# 780-00029_rev2_Pg3_Backplane_Instrument_.net
KiCad netlist of a schematic drawn in Altium Designer
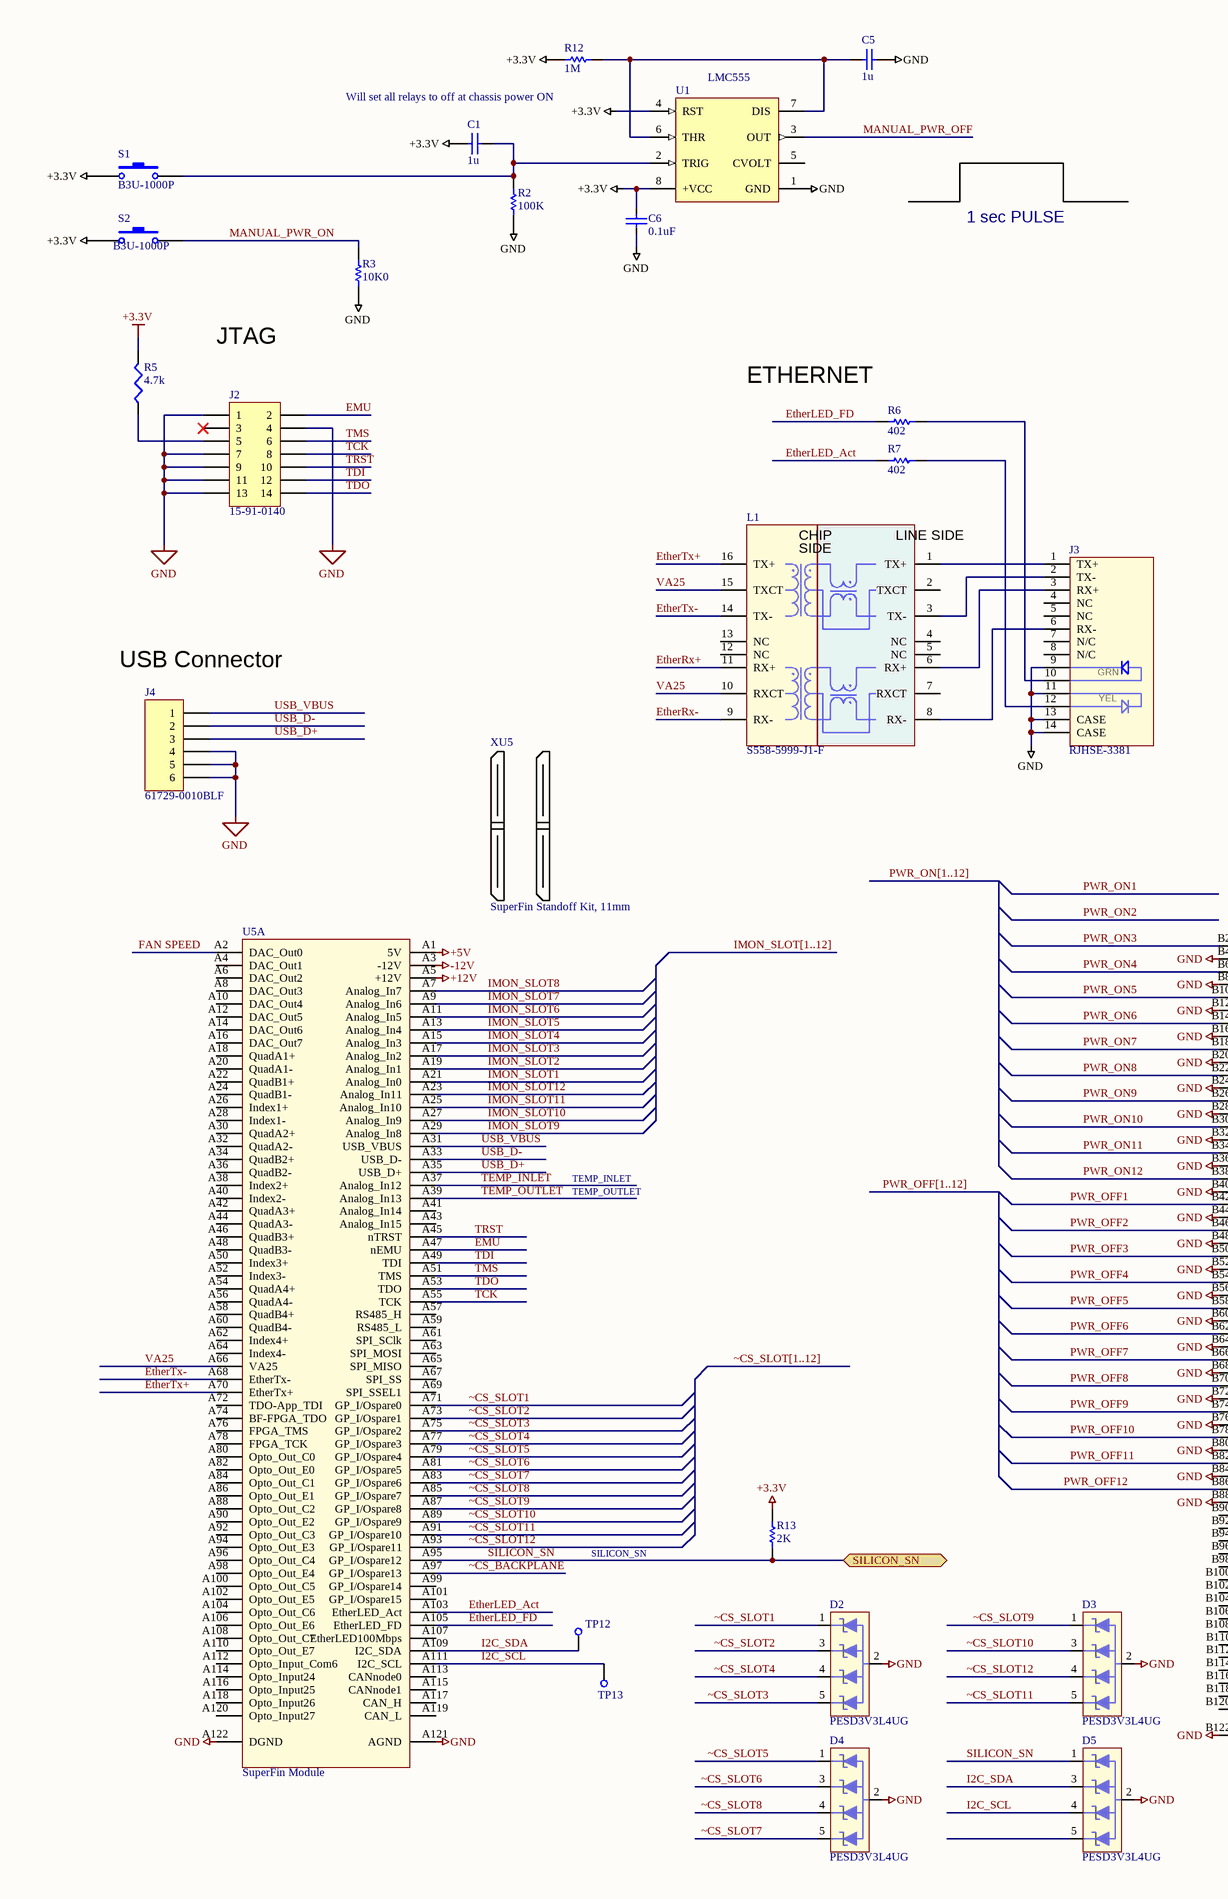
[diagram p0: 780-00029,rev2,Pg3,Backplane, Instrument Crate.SchDoc, left]
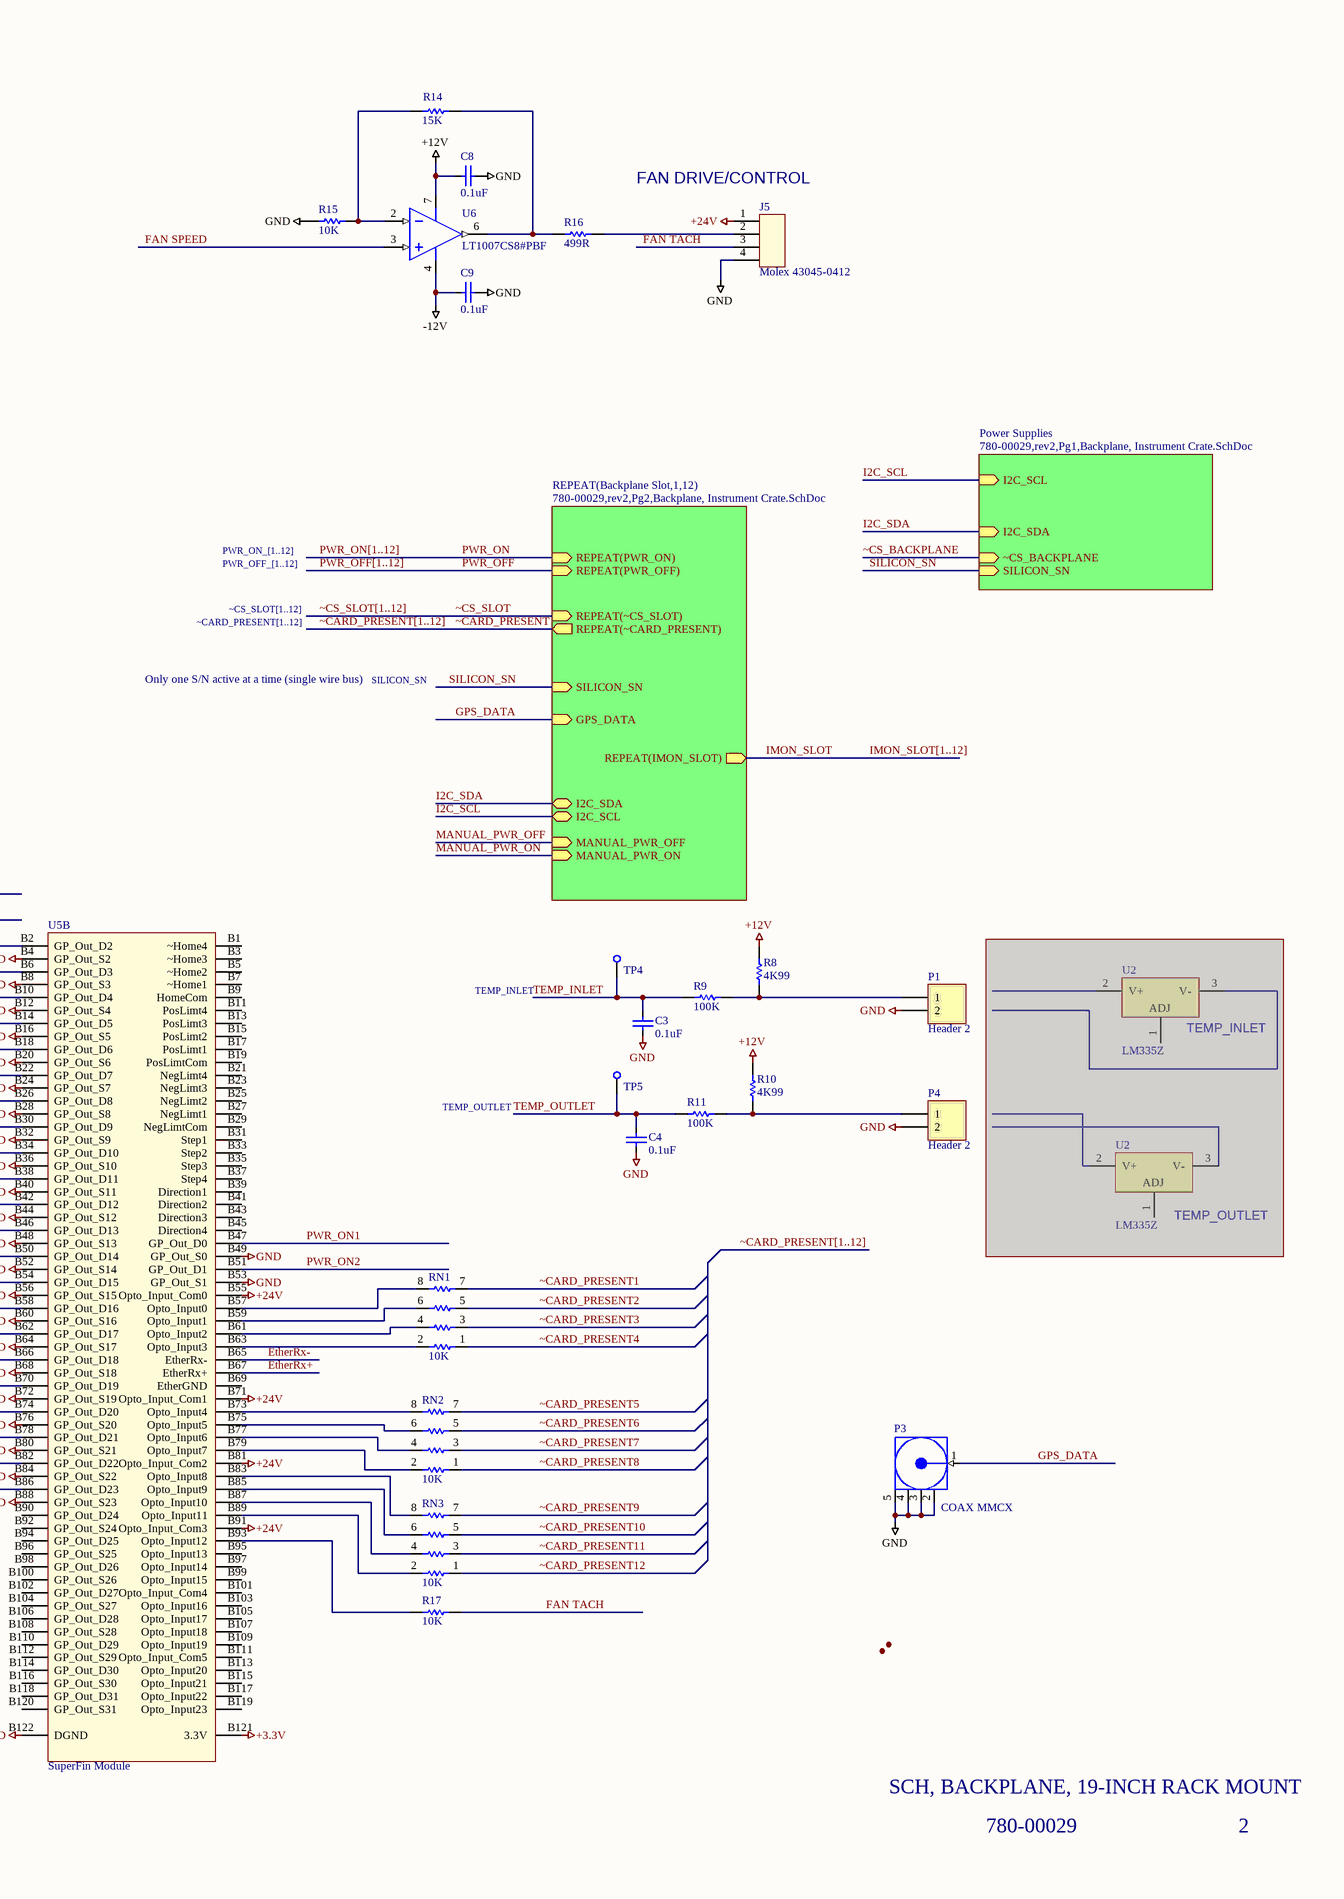
[diagram p1: 780-00029,rev2,Pg3,Backplane, Instrument Crate.SchDoc, right]

(export (version "E")
  (design (tool "Eeschema 10.0.6"))
  (components
    (comp (ref "C1")
      (value "1u")
      (footprint "2012[0805]")
      (description "Capacitor")
      (fields (field (name "MANUFACTURER") "Taiyo Yuden"))
      (libsource (lib "Miscellaneous Devices") (part "Cap"))
    )
    (comp (ref "C3")
      (value "0.1uF")
      (footprint "SMD_0805")
      (description "Capacitor")
      (fields (field (name "Comment") "Cap SMD"))
      (libsource (lib "Richs Schematic Components") (part "Cap SMD"))
    )
    (comp (ref "C4")
      (value "0.1uF")
      (footprint "SMD_0805")
      (description "Capacitor")
      (fields (field (name "Comment") "Cap SMD"))
      (libsource (lib "Richs Schematic Components") (part "Cap SMD"))
    )
    (comp (ref "C5")
      (value "1u")
      (footprint "SMD_0805")
      (description "Capacitor")
      (fields (field (name "MANUFACTURER") "Taiyo Yuden"))
      (libsource (lib "Miscellaneous Devices") (part "Cap"))
    )
    (comp (ref "C6")
      (value "0.1uF")
      (footprint "SMD_0805")
      (description "Capacitor")
      (fields (field (name "Comment") "Cap SMD"))
      (libsource (lib "Richs Schematic Components") (part "Cap SMD"))
    )
    (comp (ref "C8")
      (value "0.1uF")
      (footprint "SMD_0805")
      (description "Capacitor")
      (fields (field (name "Comment") "Cap SMD"))
      (libsource (lib "Richs Schematic Components") (part "Cap SMD"))
    )
    (comp (ref "C9")
      (value "0.1uF")
      (footprint "SMD_0805")
      (description "Capacitor")
      (fields (field (name "Comment") "Cap SMD"))
      (libsource (lib "Richs Schematic Components") (part "Cap SMD"))
    )
    (comp (ref "D2")
      (value "PESD3V3L4UG")
      (footprint "SOT-353")
      (description "Quad ESD Diode 3.3V")
      (fields (field (name "MANUFACTURER") "NXP"))
      (libsource (lib "Richs Schematic Components") (part "ESD Diode 3.3V Quad"))
    )
    (comp (ref "D3")
      (value "PESD3V3L4UG")
      (footprint "SOT-353")
      (description "Quad ESD Diode 3.3V")
      (fields (field (name "MANUFACTURER") "NXP"))
      (libsource (lib "Richs Schematic Components") (part "ESD Diode 3.3V Quad"))
    )
    (comp (ref "D4")
      (value "PESD3V3L4UG")
      (footprint "SOT-353")
      (description "Quad ESD Diode 3.3V")
      (fields (field (name "MANUFACTURER") "NXP"))
      (libsource (lib "Richs Schematic Components") (part "ESD Diode 3.3V Quad"))
    )
    (comp (ref "D5")
      (value "PESD3V3L4UG")
      (footprint "SOT-353")
      (description "Quad ESD Diode 3.3V")
      (fields (field (name "MANUFACTURER") "NXP"))
      (libsource (lib "Richs Schematic Components") (part "ESD Diode 3.3V Quad"))
    )
    (comp (ref "J2")
      (value "15-91-0140")
      (footprint "HDR2X7")
      (description "Header, 7-Pin, Dual row")
      (fields (field (name "MANUFACTURER") "Molex/Waldom"))
      (libsource (lib "Miscellaneous Connectors") (part "Header 7X2"))
    )
    (comp (ref "J3")
      (value "RJHSE-3381")
      (footprint "RJ45, VERT MOUNT, NO MAGNETICS")
      (description "Vertical PC mount, w/o magnetics")
      (libsource (lib "Richs Schematic Components") (part "CONN RJ-45 w/o magnetics"))
    )
    (comp (ref "J4")
      (value "61729-0010BLF")
      (footprint "USB Vertical PCB")
      (description "Header, 6-Pin")
      (fields (field (name "MANUFACTURER") "FCI"))
      (libsource (lib "Miscellaneous Connectors") (part "Header 6"))
    )
    (comp (ref "J5")
      (value "Molex 43045-0412")
      (footprint "CONN Molex Micro-fit, 4 POS")
      (description "Molex Micro Fit 3, Vert PC mount")
      (fields (field (name "MANUFACTURER") "Molex"))
      (libsource (lib "Richs Schematic Components") (part "CONN 4 pin 3mm"))
    )
    (comp (ref "L1")
      (value "S558-5999-J1-F")
      (footprint "10/100BT Magetics module")
      (description "10/100BT Magnetics Module")
      (libsource (lib "Richs Schematic Components") (part "Ethernet Magnetics module"))
    )
    (comp (ref "P1")
      (value "Header 2")
      (footprint "HDR1X2 for IDC")
      (description "Header, 2-Pin")
      (fields (field (name "MANUFACTURER") "TE Connectivity"))
      (libsource (lib "Richs Schematic Components") (part "Header 2"))
    )
    (comp (ref "P3")
      (value "COAX MMCX")
      (footprint "Miscellaneous Connectors:MMCX2.54-V5")
      (description "RF Coaxial PCB Connector, MMCX; Thru-Hole, Vertical Mount Plug,  50 Ohm Impedance")
      (fields (field (name "MANUFACTURER") "Emerson"))
      (libsource (lib "Richs Schematic Components") (part "COAX-M"))
    )
    (comp (ref "P4")
      (value "Header 2")
      (footprint "HDR1X2 for IDC")
      (description "Header, 2-Pin")
      (fields (field (name "MANUFACTURER") "TE Connectivity"))
      (libsource (lib "Richs Schematic Components") (part "Header 2"))
    )
    (comp (ref "R2")
      (value "100K")
      (footprint "SMD_0805")
      (description "Resistor 0805")
      (fields (field (name "MANUFACTURER") "Vishay/Dale") (field (name "Comment") "Res 0805"))
      (libsource (lib "Richs Schematic Components") (part "Res SMD"))
    )
    (comp (ref "R3")
      (value "10K0")
      (footprint "SMD_0805")
      (description "Resistor 0805")
      (fields (field (name "MANUFACTURER") "Vishay/Dale") (field (name "Comment") "Res 0805"))
      (libsource (lib "Richs Schematic Components") (part "Res SMD"))
    )
    (comp (ref "R5")
      (value "4.7k")
      (footprint "2012[0805]")
      (description "Resistor")
      (fields (field (name "MANUFACTURER") "Dale/Vishay"))
      (libsource (lib "Miscellaneous Devices") (part "Res3"))
    )
    (comp (ref "R6")
      (value "402")
      (footprint "SMD_0805")
      (description "Resistor 0805")
      (fields (field (name "MANUFACTURER") "Vishay/Dale") (field (name "Comment") "Res 0805"))
      (libsource (lib "Richs Schematic Components") (part "Res SMD"))
    )
    (comp (ref "R7")
      (value "402")
      (footprint "SMD_0805")
      (description "Resistor 0805")
      (fields (field (name "MANUFACTURER") "Vishay/Dale") (field (name "Comment") "Res 0805"))
      (libsource (lib "Richs Schematic Components") (part "Res SMD"))
    )
    (comp (ref "R8")
      (value "4K99")
      (footprint "SMD_0805")
      (description "Resistor 0805")
      (fields (field (name "MANUFACTURER") "Vishay/Dale") (field (name "Comment") "Res 0805"))
      (libsource (lib "Richs Schematic Components") (part "Res SMD"))
    )
    (comp (ref "R9")
      (value "100K")
      (footprint "SMD_0805")
      (description "Resistor 0805")
      (fields (field (name "MANUFACTURER") "Vishay/Dale") (field (name "Comment") "Res 0805"))
      (libsource (lib "Richs Schematic Components") (part "Res SMD"))
    )
    (comp (ref "R10")
      (value "4K99")
      (footprint "SMD_0805")
      (description "Resistor 0805")
      (fields (field (name "MANUFACTURER") "Vishay/Dale") (field (name "Comment") "Res 0805"))
      (libsource (lib "Richs Schematic Components") (part "Res SMD"))
    )
    (comp (ref "R11")
      (value "100K")
      (footprint "SMD_0805")
      (description "Resistor 0805")
      (fields (field (name "MANUFACTURER") "Vishay/Dale") (field (name "Comment") "Res 0805"))
      (libsource (lib "Richs Schematic Components") (part "Res SMD"))
    )
    (comp (ref "R12")
      (value "1M")
      (footprint "SMD_0805")
      (description "Resistor 0805")
      (fields (field (name "MANUFACTURER") "Vishay/Dale") (field (name "Comment") "Res 0805"))
      (libsource (lib "Richs Schematic Components") (part "Res SMD"))
    )
    (comp (ref "R13")
      (value "2K")
      (footprint "SMD_0805")
      (description "Resistor 0805")
      (fields (field (name "MANUFACTURER") "Vishay/Dale") (field (name "Comment") "Res 0805"))
      (libsource (lib "Richs Schematic Components") (part "Res SMD"))
    )
    (comp (ref "R14")
      (value "15K")
      (footprint "SMD_0805")
      (description "Resistor 0805")
      (fields (field (name "MANUFACTURER") "Vishay/Dale") (field (name "Comment") "Res 0805"))
      (libsource (lib "Richs Schematic Components") (part "Res SMD"))
    )
    (comp (ref "R15")
      (value "10K")
      (footprint "SMD_0805")
      (description "Resistor 0805")
      (fields (field (name "MANUFACTURER") "Vishay/Dale") (field (name "Comment") "Res 0805"))
      (libsource (lib "Richs Schematic Components") (part "Res SMD"))
    )
    (comp (ref "R16")
      (value "499R")
      (footprint "SMD_0805")
      (description "Resistor 0805")
      (fields (field (name "MANUFACTURER") "Vishay/Dale") (field (name "Comment") "Res 0805"))
      (libsource (lib "Richs Schematic Components") (part "Res SMD"))
    )
    (comp (ref "R17")
      (value "10K")
      (footprint "SMD_0805")
      (description "Resistor 0805")
      (fields (field (name "MANUFACTURER") "Vishay/Dale") (field (name "Comment") "Res 0805"))
      (libsource (lib "Richs Schematic Components") (part "Res SMD"))
    )
    (comp (ref "RN1")
      (value "10K")
      (footprint "RES ARRAY 0603 x 4")
      (description "Resistor Array 4 Isolated")
      (fields (field (name "MANUFACTURER") "PANASONIC - ECG") (field (name "Comment") "RES ARRAY  x4 10K"))
      (libsource (lib "Richs Schematic Components") (part "RES ARRAY  x4 10K"))
    )
    (comp (ref "RN2")
      (value "10K")
      (footprint "RES ARRAY 0603 x 4")
      (description "Resistor Array 4 Isolated")
      (fields (field (name "MANUFACTURER") "PANASONIC - ECG") (field (name "Comment") "RES ARRAY  x4 10K"))
      (libsource (lib "Richs Schematic Components") (part "RES ARRAY  x4 10K"))
    )
    (comp (ref "RN3")
      (value "10K")
      (footprint "RES ARRAY 0603 x 4")
      (description "Resistor Array 4 Isolated")
      (fields (field (name "MANUFACTURER") "PANASONIC - ECG") (field (name "Comment") "RES ARRAY  x4 10K"))
      (libsource (lib "Richs Schematic Components") (part "RES ARRAY  x4 10K"))
    )
    (comp (ref "S1")
      (value "B3U-1000P")
      (footprint "B3U-1000P")
      (description "Switch")
      (fields (field (name "MANUFACTURER") "Omron Electronics"))
      (libsource (lib "Miscellaneous Devices") (part "SW-PB"))
    )
    (comp (ref "S2")
      (value "B3U-1000P")
      (footprint "B3U-1000P")
      (description "Switch")
      (fields (field (name "MANUFACTURER") "Omron Electronics"))
      (libsource (lib "Miscellaneous Devices") (part "SW-PB"))
    )
    (comp (ref "TP4")
      (value "Test Point SMD")
      (footprint "SMD_TEST POINT")
      (description "SMD loop test point")
      (libsource (lib "Richs Schematic Components") (part "Test Point SMD"))
    )
    (comp (ref "TP5")
      (value "Test Point SMD")
      (footprint "SMD_TEST POINT")
      (description "SMD loop test point")
      (libsource (lib "Richs Schematic Components") (part "Test Point SMD"))
    )
    (comp (ref "TP12")
      (value "Test Point SMD")
      (footprint "SMD_TEST POINT")
      (description "SMD loop test point")
      (libsource (lib "Richs Schematic Components") (part "Test Point SMD"))
    )
    (comp (ref "TP13")
      (value "Test Point SMD")
      (footprint "SMD_TEST POINT")
      (description "SMD loop test point")
      (libsource (lib "Richs Schematic Components") (part "Test Point SMD"))
    )
    (comp (ref "U1")
      (value "LMC555")
      (footprint "M08A_M")
      (description "Timer")
      (fields (field (name "MANUFACTURER") "National Semiconductor") (field (name "Comment") "LM555CMX"))
      (libsource (lib "NSC Analog") (part "LM555CMX"))
    )
    (comp (ref "U2")
      (value "LM335Z")
      (footprint "Z03A")
      (description "Precision Temperature Sensor")
      (fields (field (name "MANUFACTURER") "National Semiconductor"))
      (libsource (lib "NSC Temperature Sensor") (part "LM335Z"))
    )
    (comp (ref "U5")
      (value "SuperFin Module")
      (footprint "SuperFin Footprint")
      (libsource (lib "Richs Schematic Components") (part "SuperFin Module"))
    )
    (comp (ref "U6")
      (value "LT1007CS8#PBF")
      (footprint "S8_M")
      (description "Low Noise BJT input opamp")
      (fields (field (name "MANUFACTURER") "Linear Tech"))
      (libsource (lib "Richs Schematic Components") (part "LT1007CS8#PBF"))
    )
    (comp (ref "XU5")
      (value "SuperFin Standoff Kit, 11mm")
      (libsource (lib "Richs Schematic Components") (part "SuperFin Standoff Kit, 11mm"))
    )
  )
  (nets
    (net (code "1") (name "+3.3V") (class "Default")
      (node (ref "C1") (pin "1") (pinfunction "1_1") (pintype "passive"))
      (node (ref "C6") (pin "2") (pinfunction "2_2") (pintype "passive"))
      (node (ref "R12") (pin "1") (pinfunction "1_1") (pintype "passive"))
      (node (ref "R13") (pin "2") (pinfunction "2_2") (pintype "passive"))
      (node (ref "R5") (pin "2") (pinfunction "2_2") (pintype "passive"))
      (node (ref "S1") (pin "1") (pinfunction "1_1") (pintype "passive"))
      (node (ref "S2") (pin "1") (pinfunction "1_1") (pintype "passive"))
      (node (ref "U1") (pin "4") (pinfunction "RST_4") (pintype "input"))
      (node (ref "U1") (pin "8") (pinfunction "+VCC_8") (pintype "power_in"))
      (node (ref "U5") (pin "B121") (pinfunction "3.3V_B121") (pintype "passive"))
    )
    (net (code "2") (name "+5V") (class "Default")
      (node (ref "U5") (pin "A1") (pinfunction "5V_A1") (pintype "passive"))
    )
    (net (code "3") (name "+12V") (class "Default")
      (node (ref "C8") (pin "1") (pinfunction "1_1") (pintype "passive"))
      (node (ref "R10") (pin "2") (pinfunction "2_2") (pintype "passive"))
      (node (ref "R8") (pin "2") (pinfunction "2_2") (pintype "passive"))
      (node (ref "U5") (pin "A5") (pinfunction "+12V_A5") (pintype "passive"))
      (node (ref "U6") (pin "7") (pinfunction "V+_7") (pintype "power_in"))
    )
    (net (code "4") (name "+24V") (class "Default")
      (node (ref "J5") (pin "1") (pintype "passive"))
      (node (ref "U5") (pin "B55") (pinfunction "Opto_Input_Com0_B55") (pintype "passive"))
      (node (ref "U5") (pin "B71") (pinfunction "Opto_Input_Com1_B71") (pintype "passive"))
      (node (ref "U5") (pin "B81") (pinfunction "Opto_Input_Com2_B81") (pintype "passive"))
      (node (ref "U5") (pin "B91") (pinfunction "Opto_Input_Com3_B91") (pintype "passive"))
    )
    (net (code "5") (name "-12V") (class "Default")
      (node (ref "C9") (pin "1") (pinfunction "1_1") (pintype "passive"))
      (node (ref "U5") (pin "A3") (pinfunction "-12V_A3") (pintype "passive"))
      (node (ref "U6") (pin "4") (pinfunction "V-_4") (pintype "power_in"))
    )
    (net (code "6") (name "/EMU") (class "Default")
      (node (ref "J2") (pin "2") (pinfunction "2_2") (pintype "passive"))
      (node (ref "U5") (pin "A47") (pinfunction "nEMU_A47") (pintype "passive"))
    )
    (net (code "7") (name "/EtherLED_Act") (class "Default")
      (node (ref "R7") (pin "1") (pinfunction "1_1") (pintype "passive"))
      (node (ref "U5") (pin "A103") (pinfunction "EtherLED_Act_A103") (pintype "passive"))
    )
    (net (code "8") (name "/EtherLED_FD") (class "Default")
      (node (ref "R6") (pin "1") (pinfunction "1_1") (pintype "passive"))
      (node (ref "U5") (pin "A105") (pinfunction "EtherLED_FD_A105") (pintype "passive"))
    )
    (net (code "9") (name "/EtherRx+") (class "Default")
      (node (ref "L1") (pin "11") (pinfunction "RX+_11") (pintype "passive"))
      (node (ref "U5") (pin "B67") (pinfunction "EtherRx+_B67") (pintype "passive"))
    )
    (net (code "10") (name "/EtherRx-") (class "Default")
      (node (ref "L1") (pin "9") (pinfunction "RX-_9") (pintype "passive"))
      (node (ref "U5") (pin "B65") (pinfunction "EtherRx-_B65") (pintype "passive"))
    )
    (net (code "11") (name "/EtherTx+") (class "Default")
      (node (ref "L1") (pin "16") (pinfunction "TX+_16") (pintype "passive"))
      (node (ref "U5") (pin "A70") (pinfunction "EtherTx+_A70") (pintype "passive"))
    )
    (net (code "12") (name "/EtherTx-") (class "Default")
      (node (ref "L1") (pin "14") (pinfunction "TX-_14") (pintype "passive"))
      (node (ref "U5") (pin "A68") (pinfunction "EtherTx-_A68") (pintype "passive"))
    )
    (net (code "13") (name "/FAN SPEED") (class "Default")
      (node (ref "U5") (pin "A2") (pinfunction "DAC_Out0_A2") (pintype "passive"))
      (node (ref "U6") (pin "3") (pinfunction "IN+_3") (pintype "input"))
    )
    (net (code "14") (name "/FAN TACH") (class "Default")
      (node (ref "J5") (pin "3") (pintype "passive"))
      (node (ref "R17") (pin "2") (pinfunction "2_2") (pintype "passive"))
    )
    (net (code "15") (name "/GPS_DATA") (class "Default")
      (node (ref "P3") (pin "1") (pinfunction "Signal_1") (pintype "input"))
    )
    (net (code "16") (name "/I2C_SCL") (class "Default")
      (node (ref "D5") (pin "4") (pintype "passive"))
      (node (ref "TP13") (pin "1") (pinfunction "TP_1") (pintype "passive"))
      (node (ref "U5") (pin "A111") (pinfunction "I2C_SCL_A111") (pintype "passive"))
    )
    (net (code "17") (name "/I2C_SDA") (class "Default")
      (node (ref "D5") (pin "3") (pintype "passive"))
      (node (ref "TP12") (pin "1") (pinfunction "TP_1") (pintype "passive"))
      (node (ref "U5") (pin "A109") (pinfunction "I2C_SDA_A109") (pintype "passive"))
    )
    (net (code "19") (name "/IMON_SLOT1") (class "Default")
      (node (ref "U5") (pin "A21") (pinfunction "Analog_In0_A21") (pintype "passive"))
    )
    (net (code "20") (name "/IMON_SLOT2") (class "Default")
      (node (ref "U5") (pin "A19") (pinfunction "Analog_In1_A19") (pintype "passive"))
    )
    (net (code "21") (name "/IMON_SLOT3") (class "Default")
      (node (ref "U5") (pin "A17") (pinfunction "Analog_In2_A17") (pintype "passive"))
    )
    (net (code "22") (name "/IMON_SLOT4") (class "Default")
      (node (ref "U5") (pin "A15") (pinfunction "Analog_In3_A15") (pintype "passive"))
    )
    (net (code "23") (name "/IMON_SLOT5") (class "Default")
      (node (ref "U5") (pin "A13") (pinfunction "Analog_In4_A13") (pintype "passive"))
    )
    (net (code "24") (name "/IMON_SLOT6") (class "Default")
      (node (ref "U5") (pin "A11") (pinfunction "Analog_In5_A11") (pintype "passive"))
    )
    (net (code "25") (name "/IMON_SLOT7") (class "Default")
      (node (ref "U5") (pin "A9") (pinfunction "Analog_In6_A9") (pintype "passive"))
    )
    (net (code "26") (name "/IMON_SLOT8") (class "Default")
      (node (ref "U5") (pin "A7") (pinfunction "Analog_In7_A7") (pintype "passive"))
    )
    (net (code "27") (name "/IMON_SLOT9") (class "Default")
      (node (ref "U5") (pin "A29") (pinfunction "Analog_In8_A29") (pintype "passive"))
    )
    (net (code "28") (name "/IMON_SLOT10") (class "Default")
      (node (ref "U5") (pin "A27") (pinfunction "Analog_In9_A27") (pintype "passive"))
    )
    (net (code "29") (name "/IMON_SLOT11") (class "Default")
      (node (ref "U5") (pin "A25") (pinfunction "Analog_In10_A25") (pintype "passive"))
    )
    (net (code "30") (name "/IMON_SLOT12") (class "Default")
      (node (ref "U5") (pin "A23") (pinfunction "Analog_In11_A23") (pintype "passive"))
    )
    (net (code "32") (name "/MANUAL_PWR_OFF") (class "Default")
      (node (ref "U1") (pin "3") (pinfunction "OUT_3") (pintype "output"))
    )
    (net (code "33") (name "/MANUAL_PWR_ON") (class "Default")
      (node (ref "R3") (pin "2") (pinfunction "2_2") (pintype "passive"))
      (node (ref "S2") (pin "2") (pinfunction "2_2") (pintype "passive"))
    )
    (net (code "35") (name "/PWR_OFF1") (class "Default")
      (node (ref "U5") (pin "B42") (pinfunction "GP_Out_D12_B42") (pintype "passive"))
    )
    (net (code "36") (name "/PWR_OFF2") (class "Default")
      (node (ref "U5") (pin "B46") (pinfunction "GP_Out_D13_B46") (pintype "passive"))
    )
    (net (code "37") (name "/PWR_OFF3") (class "Default")
      (node (ref "U5") (pin "B50") (pinfunction "GP_Out_D14_B50") (pintype "passive"))
    )
    (net (code "38") (name "/PWR_OFF4") (class "Default")
      (node (ref "U5") (pin "B54") (pinfunction "GP_Out_D15_B54") (pintype "passive"))
    )
    (net (code "39") (name "/PWR_OFF5") (class "Default")
      (node (ref "U5") (pin "B58") (pinfunction "GP_Out_D16_B58") (pintype "passive"))
    )
    (net (code "40") (name "/PWR_OFF6") (class "Default")
      (node (ref "U5") (pin "B62") (pinfunction "GP_Out_D17_B62") (pintype "passive"))
    )
    (net (code "41") (name "/PWR_OFF7") (class "Default")
      (node (ref "U5") (pin "B66") (pinfunction "GP_Out_D18_B66") (pintype "passive"))
    )
    (net (code "42") (name "/PWR_OFF8") (class "Default")
      (node (ref "U5") (pin "B70") (pinfunction "GP_Out_D19_B70") (pintype "passive"))
    )
    (net (code "43") (name "/PWR_OFF9") (class "Default")
      (node (ref "U5") (pin "B74") (pinfunction "GP_Out_D20_B74") (pintype "passive"))
    )
    (net (code "44") (name "/PWR_OFF10") (class "Default")
      (node (ref "U5") (pin "B78") (pinfunction "GP_Out_D21_B78") (pintype "passive"))
    )
    (net (code "45") (name "/PWR_OFF11") (class "Default")
      (node (ref "U5") (pin "B82") (pinfunction "GP_Out_D22_B82") (pintype "passive"))
    )
    (net (code "46") (name "/PWR_OFF12") (class "Default")
      (node (ref "U5") (pin "B86") (pinfunction "GP_Out_D23_B86") (pintype "passive"))
    )
    (net (code "49") (name "/PWR_ON1") (class "Default")
      (node (ref "U5") (pin "B47") (pinfunction "GP_Out_D0_B47") (pintype "passive"))
    )
    (net (code "50") (name "/PWR_ON2") (class "Default")
      (node (ref "U5") (pin "B51") (pinfunction "GP_Out_D1_B51") (pintype "passive"))
    )
    (net (code "51") (name "/PWR_ON3") (class "Default")
      (node (ref "U5") (pin "B2") (pinfunction "GP_Out_D2_B2") (pintype "passive"))
    )
    (net (code "52") (name "/PWR_ON4") (class "Default")
      (node (ref "U5") (pin "B6") (pinfunction "GP_Out_D3_B6") (pintype "passive"))
    )
    (net (code "53") (name "/PWR_ON5") (class "Default")
      (node (ref "U5") (pin "B10") (pinfunction "GP_Out_D4_B10") (pintype "passive"))
    )
    (net (code "54") (name "/PWR_ON6") (class "Default")
      (node (ref "U5") (pin "B14") (pinfunction "GP_Out_D5_B14") (pintype "passive"))
    )
    (net (code "55") (name "/PWR_ON7") (class "Default")
      (node (ref "U5") (pin "B18") (pinfunction "GP_Out_D6_B18") (pintype "passive"))
    )
    (net (code "56") (name "/PWR_ON8") (class "Default")
      (node (ref "U5") (pin "B22") (pinfunction "GP_Out_D7_B22") (pintype "passive"))
    )
    (net (code "57") (name "/PWR_ON9") (class "Default")
      (node (ref "U5") (pin "B26") (pinfunction "GP_Out_D8_B26") (pintype "passive"))
    )
    (net (code "58") (name "/PWR_ON10") (class "Default")
      (node (ref "U5") (pin "B30") (pinfunction "GP_Out_D9_B30") (pintype "passive"))
    )
    (net (code "59") (name "/PWR_ON11") (class "Default")
      (node (ref "U5") (pin "B34") (pinfunction "GP_Out_D10_B34") (pintype "passive"))
    )
    (net (code "60") (name "/PWR_ON12") (class "Default")
      (node (ref "U5") (pin "B38") (pinfunction "GP_Out_D11_B38") (pintype "passive"))
    )
    (net (code "62") (name "/SILICON_SN") (class "Default")
      (node (ref "D5") (pin "1") (pintype "passive"))
      (node (ref "R13") (pin "1") (pinfunction "1_1") (pintype "passive"))
      (node (ref "U5") (pin "A95") (pinfunction "GP_I/Ospare12_A95") (pintype "passive"))
    )
    (net (code "63") (name "/TCK") (class "Default")
      (node (ref "J2") (pin "8") (pinfunction "8_8") (pintype "passive"))
      (node (ref "U5") (pin "A55") (pinfunction "TCK_A55") (pintype "passive"))
    )
    (net (code "64") (name "/TDI") (class "Default")
      (node (ref "J2") (pin "12") (pinfunction "12_12") (pintype "passive"))
      (node (ref "U5") (pin "A49") (pinfunction "TDI_A49") (pintype "passive"))
    )
    (net (code "65") (name "/TDO") (class "Default")
      (node (ref "J2") (pin "14") (pinfunction "14_14") (pintype "passive"))
      (node (ref "U5") (pin "A53") (pinfunction "TDO_A53") (pintype "passive"))
    )
    (net (code "66") (name "/TEMP_INLET") (class "Default")
      (node (ref "C3") (pin "2") (pinfunction "2_2") (pintype "passive"))
      (node (ref "R9") (pin "1") (pinfunction "1_1") (pintype "passive"))
      (node (ref "TP4") (pin "1") (pinfunction "TP_1") (pintype "passive"))
      (node (ref "U5") (pin "A37") (pinfunction "Analog_In12_A37") (pintype "passive"))
    )
    (net (code "67") (name "/TEMP_OUTLET") (class "Default")
      (node (ref "C4") (pin "2") (pinfunction "2_2") (pintype "passive"))
      (node (ref "R11") (pin "1") (pinfunction "1_1") (pintype "passive"))
      (node (ref "TP5") (pin "1") (pinfunction "TP_1") (pintype "passive"))
      (node (ref "U5") (pin "A39") (pinfunction "Analog_In13_A39") (pintype "passive"))
    )
    (net (code "68") (name "/TMS") (class "Default")
      (node (ref "J2") (pin "6") (pinfunction "6_6") (pintype "passive"))
      (node (ref "U5") (pin "A51") (pinfunction "TMS_A51") (pintype "passive"))
    )
    (net (code "69") (name "/TRST") (class "Default")
      (node (ref "J2") (pin "10") (pinfunction "10_10") (pintype "passive"))
      (node (ref "U5") (pin "A45") (pinfunction "nTRST_A45") (pintype "passive"))
    )
    (net (code "70") (name "/USB_D+") (class "Default")
      (node (ref "J4") (pin "3") (pinfunction "3_3") (pintype "passive"))
      (node (ref "U5") (pin "A35") (pinfunction "USB_D+_A35") (pintype "passive"))
    )
    (net (code "71") (name "/USB_D-") (class "Default")
      (node (ref "J4") (pin "2") (pinfunction "2_2") (pintype "passive"))
      (node (ref "U5") (pin "A33") (pinfunction "USB_D-_A33") (pintype "passive"))
    )
    (net (code "72") (name "/USB_VBUS") (class "Default")
      (node (ref "J4") (pin "1") (pinfunction "1_1") (pintype "passive"))
      (node (ref "U5") (pin "A31") (pinfunction "USB_VBUS_A31") (pintype "passive"))
    )
    (net (code "73") (name "/VA25") (class "Default")
      (node (ref "L1") (pin "10") (pinfunction "RXCT_10") (pintype "passive"))
      (node (ref "L1") (pin "15") (pinfunction "TXCT_15") (pintype "passive"))
      (node (ref "U5") (pin "A66") (pinfunction "VA25_A66") (pintype "passive"))
    )
    (net (code "75") (name "/~CARD_PRESENT1") (class "Default")
      (node (ref "RN1") (pin "7") (pinfunction "1_7") (pintype "passive"))
    )
    (net (code "76") (name "/~CARD_PRESENT2") (class "Default")
      (node (ref "RN1") (pin "5") (pinfunction "5_5") (pintype "passive"))
    )
    (net (code "77") (name "/~CARD_PRESENT3") (class "Default")
      (node (ref "RN1") (pin "3") (pinfunction "3_3") (pintype "passive"))
    )
    (net (code "78") (name "/~CARD_PRESENT4") (class "Default")
      (node (ref "RN1") (pin "1") (pinfunction "1_1") (pintype "passive"))
    )
    (net (code "79") (name "/~CARD_PRESENT5") (class "Default")
      (node (ref "RN2") (pin "7") (pinfunction "1_7") (pintype "passive"))
    )
    (net (code "80") (name "/~CARD_PRESENT6") (class "Default")
      (node (ref "RN2") (pin "5") (pinfunction "5_5") (pintype "passive"))
    )
    (net (code "81") (name "/~CARD_PRESENT7") (class "Default")
      (node (ref "RN2") (pin "3") (pinfunction "3_3") (pintype "passive"))
    )
    (net (code "82") (name "/~CARD_PRESENT8") (class "Default")
      (node (ref "RN2") (pin "1") (pinfunction "1_1") (pintype "passive"))
    )
    (net (code "83") (name "/~CARD_PRESENT9") (class "Default")
      (node (ref "RN3") (pin "7") (pinfunction "1_7") (pintype "passive"))
    )
    (net (code "84") (name "/~CARD_PRESENT10") (class "Default")
      (node (ref "RN3") (pin "5") (pinfunction "5_5") (pintype "passive"))
    )
    (net (code "85") (name "/~CARD_PRESENT11") (class "Default")
      (node (ref "RN3") (pin "3") (pinfunction "3_3") (pintype "passive"))
    )
    (net (code "86") (name "/~CARD_PRESENT12") (class "Default")
      (node (ref "RN3") (pin "1") (pinfunction "1_1") (pintype "passive"))
    )
    (net (code "88") (name "/~CS_BACKPLANE") (class "Default")
      (node (ref "U5") (pin "A97") (pinfunction "GP_I/Ospare13_A97") (pintype "passive"))
    )
    (net (code "90") (name "/~CS_SLOT1") (class "Default")
      (node (ref "D2") (pin "1") (pintype "passive"))
      (node (ref "U5") (pin "A71") (pinfunction "GP_I/Ospare0_A71") (pintype "passive"))
    )
    (net (code "91") (name "/~CS_SLOT2") (class "Default")
      (node (ref "D2") (pin "3") (pintype "passive"))
      (node (ref "U5") (pin "A73") (pinfunction "GP_I/Ospare1_A73") (pintype "passive"))
    )
    (net (code "92") (name "/~CS_SLOT3") (class "Default")
      (node (ref "D2") (pin "5") (pintype "passive"))
      (node (ref "U5") (pin "A75") (pinfunction "GP_I/Ospare2_A75") (pintype "passive"))
    )
    (net (code "93") (name "/~CS_SLOT4") (class "Default")
      (node (ref "D2") (pin "4") (pintype "passive"))
      (node (ref "U5") (pin "A77") (pinfunction "GP_I/Ospare3_A77") (pintype "passive"))
    )
    (net (code "94") (name "/~CS_SLOT5") (class "Default")
      (node (ref "D4") (pin "1") (pintype "passive"))
      (node (ref "U5") (pin "A79") (pinfunction "GP_I/Ospare4_A79") (pintype "passive"))
    )
    (net (code "95") (name "/~CS_SLOT6") (class "Default")
      (node (ref "D4") (pin "3") (pintype "passive"))
      (node (ref "U5") (pin "A81") (pinfunction "GP_I/Ospare5_A81") (pintype "passive"))
    )
    (net (code "96") (name "/~CS_SLOT7") (class "Default")
      (node (ref "D4") (pin "5") (pintype "passive"))
      (node (ref "U5") (pin "A83") (pinfunction "GP_I/Ospare6_A83") (pintype "passive"))
    )
    (net (code "97") (name "/~CS_SLOT8") (class "Default")
      (node (ref "D4") (pin "4") (pintype "passive"))
      (node (ref "U5") (pin "A85") (pinfunction "GP_I/Ospare7_A85") (pintype "passive"))
    )
    (net (code "98") (name "/~CS_SLOT9") (class "Default")
      (node (ref "D3") (pin "1") (pintype "passive"))
      (node (ref "U5") (pin "A87") (pinfunction "GP_I/Ospare8_A87") (pintype "passive"))
    )
    (net (code "99") (name "/~CS_SLOT10") (class "Default")
      (node (ref "D3") (pin "3") (pintype "passive"))
      (node (ref "U5") (pin "A89") (pinfunction "GP_I/Ospare9_A89") (pintype "passive"))
    )
    (net (code "100") (name "/~CS_SLOT11") (class "Default")
      (node (ref "D3") (pin "5") (pintype "passive"))
      (node (ref "U5") (pin "A91") (pinfunction "GP_I/Ospare10_A91") (pintype "passive"))
    )
    (net (code "101") (name "/~CS_SLOT12") (class "Default")
      (node (ref "D3") (pin "4") (pintype "passive"))
      (node (ref "U5") (pin "A93") (pinfunction "GP_I/Ospare11_A93") (pintype "passive"))
    )
    (net (code "103") (name "GND") (class "Default")
      (node (ref "C3") (pin "1") (pinfunction "1_1") (pintype "passive"))
      (node (ref "C4") (pin "1") (pinfunction "1_1") (pintype "passive"))
      (node (ref "C5") (pin "2") (pinfunction "2_2") (pintype "passive"))
      (node (ref "C6") (pin "1") (pinfunction "1_1") (pintype "passive"))
      (node (ref "C8") (pin "2") (pinfunction "2_2") (pintype "passive"))
      (node (ref "C9") (pin "2") (pinfunction "2_2") (pintype "passive"))
      (node (ref "D2") (pin "2") (pintype "passive"))
      (node (ref "D3") (pin "2") (pintype "passive"))
      (node (ref "D4") (pin "2") (pintype "passive"))
      (node (ref "D5") (pin "2") (pintype "passive"))
      (node (ref "J2") (pin "1") (pinfunction "1_1") (pintype "passive"))
      (node (ref "J2") (pin "11") (pinfunction "11_11") (pintype "passive"))
      (node (ref "J2") (pin "13") (pinfunction "13_13") (pintype "passive"))
      (node (ref "J2") (pin "4") (pinfunction "4_4") (pintype "passive"))
      (node (ref "J2") (pin "7") (pinfunction "7_7") (pintype "passive"))
      (node (ref "J2") (pin "9") (pinfunction "9_9") (pintype "passive"))
      (node (ref "J3") (pin "11") (pinfunction "YEL-Cathode_11") (pintype "passive"))
      (node (ref "J3") (pin "13") (pinfunction "CASE_13") (pintype "passive"))
      (node (ref "J3") (pin "14") (pinfunction "CASE_14") (pintype "passive"))
      (node (ref "J3") (pin "9") (pinfunction "GRN-Anode_9") (pintype "passive"))
      (node (ref "J4") (pin "4") (pinfunction "4_4") (pintype "passive"))
      (node (ref "J4") (pin "5") (pinfunction "5_5") (pintype "passive"))
      (node (ref "J4") (pin "6") (pinfunction "6_6") (pintype "passive"))
      (node (ref "J5") (pin "4") (pintype "passive"))
      (node (ref "P1") (pin "2") (pinfunction "2_2") (pintype "passive"))
      (node (ref "P3") (pin "2") (pinfunction "GND_2") (pintype "power_in"))
      (node (ref "P3") (pin "3") (pinfunction "GND_3") (pintype "power_in"))
      (node (ref "P3") (pin "4") (pinfunction "GND_4") (pintype "power_in"))
      (node (ref "P3") (pin "5") (pinfunction "GND_5") (pintype "power_in"))
      (node (ref "P4") (pin "2") (pinfunction "2_2") (pintype "passive"))
      (node (ref "R15") (pin "1") (pinfunction "1_1") (pintype "passive"))
      (node (ref "R2") (pin "1") (pinfunction "1_1") (pintype "passive"))
      (node (ref "R3") (pin "1") (pinfunction "1_1") (pintype "passive"))
      (node (ref "U1") (pin "1") (pinfunction "GND_1") (pintype "power_in"))
      (node (ref "U5") (pin "A121") (pinfunction "AGND_A121") (pintype "passive"))
      (node (ref "U5") (pin "A122") (pinfunction "DGND_A122") (pintype "passive"))
      (node (ref "U5") (pin "B12") (pinfunction "GP_Out_S4_B12") (pintype "passive"))
      (node (ref "U5") (pin "B122") (pinfunction "DGND_B122") (pintype "passive"))
      (node (ref "U5") (pin "B16") (pinfunction "GP_Out_S5_B16") (pintype "passive"))
      (node (ref "U5") (pin "B20") (pinfunction "GP_Out_S6_B20") (pintype "passive"))
      (node (ref "U5") (pin "B24") (pinfunction "GP_Out_S7_B24") (pintype "passive"))
      (node (ref "U5") (pin "B28") (pinfunction "GP_Out_S8_B28") (pintype "passive"))
      (node (ref "U5") (pin "B32") (pinfunction "GP_Out_S9_B32") (pintype "passive"))
      (node (ref "U5") (pin "B36") (pinfunction "GP_Out_S10_B36") (pintype "passive"))
      (node (ref "U5") (pin "B4") (pinfunction "GP_Out_S2_B4") (pintype "passive"))
      (node (ref "U5") (pin "B40") (pinfunction "GP_Out_S11_B40") (pintype "passive"))
      (node (ref "U5") (pin "B44") (pinfunction "GP_Out_S12_B44") (pintype "passive"))
      (node (ref "U5") (pin "B48") (pinfunction "GP_Out_S13_B48") (pintype "passive"))
      (node (ref "U5") (pin "B49") (pinfunction "GP_Out_S0_B49") (pintype "passive"))
      (node (ref "U5") (pin "B52") (pinfunction "GP_Out_S14_B52") (pintype "passive"))
      (node (ref "U5") (pin "B53") (pinfunction "GP_Out_S1_B53") (pintype "passive"))
      (node (ref "U5") (pin "B56") (pinfunction "GP_Out_S15_B56") (pintype "passive"))
      (node (ref "U5") (pin "B60") (pinfunction "GP_Out_S16_B60") (pintype "passive"))
      (node (ref "U5") (pin "B64") (pinfunction "GP_Out_S17_B64") (pintype "passive"))
      (node (ref "U5") (pin "B68") (pinfunction "GP_Out_S18_B68") (pintype "passive"))
      (node (ref "U5") (pin "B72") (pinfunction "GP_Out_S19_B72") (pintype "passive"))
      (node (ref "U5") (pin "B76") (pinfunction "GP_Out_S20_B76") (pintype "passive"))
      (node (ref "U5") (pin "B8") (pinfunction "GP_Out_S3_B8") (pintype "passive"))
      (node (ref "U5") (pin "B80") (pinfunction "GP_Out_S21_B80") (pintype "passive"))
      (node (ref "U5") (pin "B84") (pinfunction "GP_Out_S22_B84") (pintype "passive"))
      (node (ref "U5") (pin "B88") (pinfunction "GP_Out_S23_B88") (pintype "passive"))
    )
    (net (code "104") (name "Net-(J2-Pad5)") (class "Default")
      (node (ref "J2") (pin "5") (pinfunction "5_5") (pintype "passive"))
      (node (ref "R5") (pin "1") (pinfunction "1_1") (pintype "passive"))
    )
    (net (code "105") (name "Net-(J3-GRN-Cathode)") (class "Default")
      (node (ref "J3") (pin "10") (pinfunction "GRN-Cathode_10") (pintype "passive"))
      (node (ref "R6") (pin "2") (pinfunction "2_2") (pintype "passive"))
    )
    (net (code "106") (name "Net-(J3-RX+)") (class "Default")
      (node (ref "J3") (pin "3") (pinfunction "RX+_3") (pintype "passive"))
      (node (ref "L1") (pin "6") (pinfunction "RX+_6") (pintype "passive"))
    )
    (net (code "107") (name "Net-(J3-RX-)") (class "Default")
      (node (ref "J3") (pin "6") (pinfunction "RX-_6") (pintype "passive"))
      (node (ref "L1") (pin "8") (pinfunction "RX-_8") (pintype "passive"))
    )
    (net (code "108") (name "Net-(J3-TX+)") (class "Default")
      (node (ref "J3") (pin "1") (pinfunction "TX+_1") (pintype "passive"))
      (node (ref "L1") (pin "1") (pinfunction "TX+_1") (pintype "passive"))
    )
    (net (code "109") (name "Net-(J3-TX-)") (class "Default")
      (node (ref "J3") (pin "2") (pinfunction "TX-_2") (pintype "passive"))
      (node (ref "L1") (pin "3") (pinfunction "TX-_3") (pintype "passive"))
    )
    (net (code "110") (name "Net-(J3-YEL-Anode)") (class "Default")
      (node (ref "J3") (pin "12") (pinfunction "YEL-Anode_12") (pintype "passive"))
      (node (ref "R7") (pin "2") (pinfunction "2_2") (pintype "passive"))
    )
    (net (code "111") (name "Net-(J5-Pad2)") (class "Default")
      (node (ref "J5") (pin "2") (pintype "passive"))
      (node (ref "R16") (pin "1") (pinfunction "1_1") (pintype "passive"))
    )
    (net (code "112") (name "Net-(P1-Pad1)") (class "Default")
      (node (ref "P1") (pin "1") (pinfunction "1_1") (pintype "passive"))
      (node (ref "R8") (pin "1") (pinfunction "1_1") (pintype "passive"))
      (node (ref "R9") (pin "2") (pinfunction "2_2") (pintype "passive"))
    )
    (net (code "113") (name "Net-(P4-Pad1)") (class "Default")
      (node (ref "P4") (pin "1") (pinfunction "1_1") (pintype "passive"))
      (node (ref "R10") (pin "1") (pinfunction "1_1") (pintype "passive"))
      (node (ref "R11") (pin "2") (pinfunction "2_2") (pintype "passive"))
    )
    (net (code "114") (name "Net-(U1-DIS)") (class "Default")
      (node (ref "C5") (pin "1") (pinfunction "1_1") (pintype "passive"))
      (node (ref "R12") (pin "2") (pinfunction "2_2") (pintype "passive"))
      (node (ref "U1") (pin "6") (pinfunction "THR_6") (pintype "input"))
      (node (ref "U1") (pin "7") (pinfunction "DIS_7") (pintype "open_collector"))
    )
    (net (code "115") (name "Net-(U1-TRIG)") (class "Default")
      (node (ref "C1") (pin "2") (pinfunction "2_2") (pintype "passive"))
      (node (ref "R2") (pin "2") (pinfunction "2_2") (pintype "passive"))
      (node (ref "S1") (pin "2") (pinfunction "2_2") (pintype "passive"))
      (node (ref "U1") (pin "2") (pinfunction "TRIG_2") (pintype "input"))
    )
    (net (code "116") (name "Net-(U5B-Opto_Input0)") (class "Default")
      (node (ref "RN1") (pin "8") (pinfunction "8_8") (pintype "passive"))
      (node (ref "U5") (pin "B57") (pinfunction "Opto_Input0_B57") (pintype "passive"))
    )
    (net (code "117") (name "Net-(U5B-Opto_Input1)") (class "Default")
      (node (ref "RN1") (pin "6") (pinfunction "6_6") (pintype "passive"))
      (node (ref "U5") (pin "B59") (pinfunction "Opto_Input1_B59") (pintype "passive"))
    )
    (net (code "118") (name "Net-(U5B-Opto_Input2)") (class "Default")
      (node (ref "RN1") (pin "4") (pinfunction "4_4") (pintype "passive"))
      (node (ref "U5") (pin "B61") (pinfunction "Opto_Input2_B61") (pintype "passive"))
    )
    (net (code "119") (name "Net-(U5B-Opto_Input3)") (class "Default")
      (node (ref "RN1") (pin "2") (pinfunction "2_2") (pintype "passive"))
      (node (ref "U5") (pin "B63") (pinfunction "Opto_Input3_B63") (pintype "passive"))
    )
    (net (code "120") (name "Net-(U5B-Opto_Input4)") (class "Default")
      (node (ref "RN2") (pin "8") (pinfunction "8_8") (pintype "passive"))
      (node (ref "U5") (pin "B73") (pinfunction "Opto_Input4_B73") (pintype "passive"))
    )
    (net (code "121") (name "Net-(U5B-Opto_Input5)") (class "Default")
      (node (ref "RN2") (pin "6") (pinfunction "6_6") (pintype "passive"))
      (node (ref "U5") (pin "B75") (pinfunction "Opto_Input5_B75") (pintype "passive"))
    )
    (net (code "122") (name "Net-(U5B-Opto_Input6)") (class "Default")
      (node (ref "RN2") (pin "4") (pinfunction "4_4") (pintype "passive"))
      (node (ref "U5") (pin "B77") (pinfunction "Opto_Input6_B77") (pintype "passive"))
    )
    (net (code "123") (name "Net-(U5B-Opto_Input7)") (class "Default")
      (node (ref "RN2") (pin "2") (pinfunction "2_2") (pintype "passive"))
      (node (ref "U5") (pin "B79") (pinfunction "Opto_Input7_B79") (pintype "passive"))
    )
    (net (code "124") (name "Net-(U5B-Opto_Input8)") (class "Default")
      (node (ref "RN3") (pin "8") (pinfunction "8_8") (pintype "passive"))
      (node (ref "U5") (pin "B83") (pinfunction "Opto_Input8_B83") (pintype "passive"))
    )
    (net (code "125") (name "Net-(U5B-Opto_Input9)") (class "Default")
      (node (ref "RN3") (pin "6") (pinfunction "6_6") (pintype "passive"))
      (node (ref "U5") (pin "B85") (pinfunction "Opto_Input9_B85") (pintype "passive"))
    )
    (net (code "126") (name "Net-(U5B-Opto_Input10)") (class "Default")
      (node (ref "RN3") (pin "4") (pinfunction "4_4") (pintype "passive"))
      (node (ref "U5") (pin "B87") (pinfunction "Opto_Input10_B87") (pintype "passive"))
    )
    (net (code "127") (name "Net-(U5B-Opto_Input11)") (class "Default")
      (node (ref "RN3") (pin "2") (pinfunction "2_2") (pintype "passive"))
      (node (ref "U5") (pin "B89") (pinfunction "Opto_Input11_B89") (pintype "passive"))
    )
    (net (code "128") (name "Net-(U5B-Opto_Input12)") (class "Default")
      (node (ref "R17") (pin "1") (pinfunction "1_1") (pintype "passive"))
      (node (ref "U5") (pin "B93") (pinfunction "Opto_Input12_B93") (pintype "passive"))
    )
    (net (code "129") (name "Net-(U6-IN-)") (class "Default")
      (node (ref "R14") (pin "1") (pinfunction "1_1") (pintype "passive"))
      (node (ref "R15") (pin "2") (pinfunction "2_2") (pintype "passive"))
      (node (ref "U6") (pin "2") (pinfunction "IN-_2") (pintype "input"))
    )
    (net (code "130") (name "Net-(U6-OUT)") (class "Default")
      (node (ref "R14") (pin "2") (pinfunction "2_2") (pintype "passive"))
      (node (ref "R16") (pin "2") (pinfunction "2_2") (pintype "passive"))
      (node (ref "U6") (pin "6") (pinfunction "OUT_6") (pintype "output"))
    )
    (net (code "131") (name "unconnected-(D5-Pad5)") (class "Default")
      (node (ref "D5") (pin "5") (pintype "passive"))
    )
    (net (code "132") (name "unconnected-(J2-Pad3)") (class "Default")
      (node (ref "J2") (pin "3") (pinfunction "3_3") (pintype "passive+no_connect"))
    )
    (net (code "133") (name "unconnected-(J3-NC-Pad4)") (class "Default")
      (node (ref "J3") (pin "4") (pinfunction "NC_4") (pintype "passive"))
    )
    (net (code "134") (name "unconnected-(J3-NC-Pad5)") (class "Default")
      (node (ref "J3") (pin "5") (pinfunction "NC_5") (pintype "passive"))
    )
    (net (code "135") (name "unconnected-(J3-N{slash}C-Pad7)") (class "Default")
      (node (ref "J3") (pin "7") (pinfunction "N/C_7") (pintype "passive"))
    )
    (net (code "136") (name "unconnected-(J3-N{slash}C-Pad8)") (class "Default")
      (node (ref "J3") (pin "8") (pinfunction "N/C_8") (pintype "passive"))
    )
    (net (code "137") (name "unconnected-(L1-NC-Pad4)") (class "Default")
      (node (ref "L1") (pin "4") (pinfunction "NC_4") (pintype "passive"))
    )
    (net (code "138") (name "unconnected-(L1-NC-Pad5)") (class "Default")
      (node (ref "L1") (pin "5") (pinfunction "NC_5") (pintype "passive"))
    )
    (net (code "139") (name "unconnected-(L1-NC-Pad12)") (class "Default")
      (node (ref "L1") (pin "12") (pinfunction "NC_12") (pintype "passive"))
    )
    (net (code "140") (name "unconnected-(L1-NC-Pad13)") (class "Default")
      (node (ref "L1") (pin "13") (pinfunction "NC_13") (pintype "passive"))
    )
    (net (code "141") (name "unconnected-(L1-RXCT-Pad7)") (class "Default")
      (node (ref "L1") (pin "7") (pinfunction "RXCT_7") (pintype "passive"))
    )
    (net (code "142") (name "unconnected-(L1-TXCT-Pad2)") (class "Default")
      (node (ref "L1") (pin "2") (pinfunction "TXCT_2") (pintype "passive"))
    )
    (net (code "143") (name "unconnected-(U1-CVOLT-Pad5)") (class "Default")
      (node (ref "U1") (pin "5") (pinfunction "CVOLT_5") (pintype "passive"))
    )
    (net (code "144") (name "unconnected-(U2-ADJ-Pad1)") (class "Default")
      (node (ref "U2") (pin "1") (pinfunction "ADJ_1") (pintype "passive"))
    )
    (net (code "145") (name "unconnected-(U2-ADJ-Pad1)_1") (class "Default")
      (node (ref "U2") (pin "1") (pinfunction "ADJ_1") (pintype "passive"))
    )
    (net (code "146") (name "unconnected-(U2-V+-Pad2)") (class "Default")
      (node (ref "U2") (pin "2") (pinfunction "V+_2") (pintype "passive"))
    )
    (net (code "147") (name "unconnected-(U2-V+-Pad2)_1") (class "Default")
      (node (ref "U2") (pin "2") (pinfunction "V+_2") (pintype "passive"))
    )
    (net (code "148") (name "unconnected-(U2-V--Pad3)") (class "Default")
      (node (ref "U2") (pin "3") (pinfunction "V-_3") (pintype "passive"))
    )
    (net (code "149") (name "unconnected-(U2-V--Pad3)_1") (class "Default")
      (node (ref "U2") (pin "3") (pinfunction "V-_3") (pintype "passive"))
    )
    (net (code "150") (name "unconnected-(U5A-Analog_In14-PadA41)") (class "Default")
      (node (ref "U5") (pin "A41") (pinfunction "Analog_In14_A41") (pintype "passive"))
    )
    (net (code "151") (name "unconnected-(U5A-Analog_In15-PadA43)") (class "Default")
      (node (ref "U5") (pin "A43") (pinfunction "Analog_In15_A43") (pintype "passive"))
    )
    (net (code "152") (name "unconnected-(U5A-BF-FPGA_TDO-PadA74)") (class "Default")
      (node (ref "U5") (pin "A74") (pinfunction "BF-FPGA_TDO_A74") (pintype "passive"))
    )
    (net (code "153") (name "unconnected-(U5A-CAN_H-PadA117)") (class "Default")
      (node (ref "U5") (pin "A117") (pinfunction "CAN_H_A117") (pintype "passive"))
    )
    (net (code "154") (name "unconnected-(U5A-CAN_L-PadA119)") (class "Default")
      (node (ref "U5") (pin "A119") (pinfunction "CAN_L_A119") (pintype "passive"))
    )
    (net (code "155") (name "unconnected-(U5A-CANnode0-PadA113)") (class "Default")
      (node (ref "U5") (pin "A113") (pinfunction "CANnode0_A113") (pintype "passive"))
    )
    (net (code "156") (name "unconnected-(U5A-CANnode1-PadA115)") (class "Default")
      (node (ref "U5") (pin "A115") (pinfunction "CANnode1_A115") (pintype "passive"))
    )
    (net (code "157") (name "unconnected-(U5A-DAC_Out1-PadA4)") (class "Default")
      (node (ref "U5") (pin "A4") (pinfunction "DAC_Out1_A4") (pintype "passive"))
    )
    (net (code "158") (name "unconnected-(U5A-DAC_Out2-PadA6)") (class "Default")
      (node (ref "U5") (pin "A6") (pinfunction "DAC_Out2_A6") (pintype "passive"))
    )
    (net (code "159") (name "unconnected-(U5A-DAC_Out3-PadA8)") (class "Default")
      (node (ref "U5") (pin "A8") (pinfunction "DAC_Out3_A8") (pintype "passive"))
    )
    (net (code "160") (name "unconnected-(U5A-DAC_Out4-PadA10)") (class "Default")
      (node (ref "U5") (pin "A10") (pinfunction "DAC_Out4_A10") (pintype "passive"))
    )
    (net (code "161") (name "unconnected-(U5A-DAC_Out5-PadA12)") (class "Default")
      (node (ref "U5") (pin "A12") (pinfunction "DAC_Out5_A12") (pintype "passive"))
    )
    (net (code "162") (name "unconnected-(U5A-DAC_Out6-PadA14)") (class "Default")
      (node (ref "U5") (pin "A14") (pinfunction "DAC_Out6_A14") (pintype "passive"))
    )
    (net (code "163") (name "unconnected-(U5A-DAC_Out7-PadA16)") (class "Default")
      (node (ref "U5") (pin "A16") (pinfunction "DAC_Out7_A16") (pintype "passive"))
    )
    (net (code "164") (name "unconnected-(U5A-EtherLED100Mbps-PadA107)") (class "Default")
      (node (ref "U5") (pin "A107") (pinfunction "EtherLED100Mbps_A107") (pintype "passive"))
    )
    (net (code "165") (name "unconnected-(U5A-FPGA_TCK-PadA78)") (class "Default")
      (node (ref "U5") (pin "A78") (pinfunction "FPGA_TCK_A78") (pintype "passive"))
    )
    (net (code "166") (name "unconnected-(U5A-FPGA_TMS-PadA76)") (class "Default")
      (node (ref "U5") (pin "A76") (pinfunction "FPGA_TMS_A76") (pintype "passive"))
    )
    (net (code "167") (name "unconnected-(U5A-GP_I{slash}Ospare14-PadA99)") (class "Default")
      (node (ref "U5") (pin "A99") (pinfunction "GP_I/Ospare14_A99") (pintype "passive"))
    )
    (net (code "168") (name "unconnected-(U5A-GP_I{slash}Ospare15-PadA101)") (class "Default")
      (node (ref "U5") (pin "A101") (pinfunction "GP_I/Ospare15_A101") (pintype "passive"))
    )
    (net (code "169") (name "unconnected-(U5A-Index1+-PadA26)") (class "Default")
      (node (ref "U5") (pin "A26") (pinfunction "Index1+_A26") (pintype "passive"))
    )
    (net (code "170") (name "unconnected-(U5A-Index1--PadA28)") (class "Default")
      (node (ref "U5") (pin "A28") (pinfunction "Index1-_A28") (pintype "passive"))
    )
    (net (code "171") (name "unconnected-(U5A-Index2+-PadA38)") (class "Default")
      (node (ref "U5") (pin "A38") (pinfunction "Index2+_A38") (pintype "passive"))
    )
    (net (code "172") (name "unconnected-(U5A-Index2--PadA40)") (class "Default")
      (node (ref "U5") (pin "A40") (pinfunction "Index2-_A40") (pintype "passive"))
    )
    (net (code "173") (name "unconnected-(U5A-Index3+-PadA50)") (class "Default")
      (node (ref "U5") (pin "A50") (pinfunction "Index3+_A50") (pintype "passive"))
    )
    (net (code "174") (name "unconnected-(U5A-Index3--PadA52)") (class "Default")
      (node (ref "U5") (pin "A52") (pinfunction "Index3-_A52") (pintype "passive"))
    )
    (net (code "175") (name "unconnected-(U5A-Index4+-PadA62)") (class "Default")
      (node (ref "U5") (pin "A62") (pinfunction "Index4+_A62") (pintype "passive"))
    )
    (net (code "176") (name "unconnected-(U5A-Index4--PadA64)") (class "Default")
      (node (ref "U5") (pin "A64") (pinfunction "Index4-_A64") (pintype "passive"))
    )
    (net (code "177") (name "unconnected-(U5A-Opto_Input24-PadA114)") (class "Default")
      (node (ref "U5") (pin "A114") (pinfunction "Opto_Input24_A114") (pintype "passive"))
    )
    (net (code "178") (name "unconnected-(U5A-Opto_Input25-PadA116)") (class "Default")
      (node (ref "U5") (pin "A116") (pinfunction "Opto_Input25_A116") (pintype "passive"))
    )
    (net (code "179") (name "unconnected-(U5A-Opto_Input26-PadA118)") (class "Default")
      (node (ref "U5") (pin "A118") (pinfunction "Opto_Input26_A118") (pintype "passive"))
    )
    (net (code "180") (name "unconnected-(U5A-Opto_Input27-PadA120)") (class "Default")
      (node (ref "U5") (pin "A120") (pinfunction "Opto_Input27_A120") (pintype "passive"))
    )
    (net (code "181") (name "unconnected-(U5A-Opto_Input_Com6-PadA112)") (class "Default")
      (node (ref "U5") (pin "A112") (pinfunction "Opto_Input_Com6_A112") (pintype "passive"))
    )
    (net (code "182") (name "unconnected-(U5A-Opto_Out_C0-PadA80)") (class "Default")
      (node (ref "U5") (pin "A80") (pinfunction "Opto_Out_C0_A80") (pintype "passive"))
    )
    (net (code "183") (name "unconnected-(U5A-Opto_Out_C1-PadA84)") (class "Default")
      (node (ref "U5") (pin "A84") (pinfunction "Opto_Out_C1_A84") (pintype "passive"))
    )
    (net (code "184") (name "unconnected-(U5A-Opto_Out_C2-PadA88)") (class "Default")
      (node (ref "U5") (pin "A88") (pinfunction "Opto_Out_C2_A88") (pintype "passive"))
    )
    (net (code "185") (name "unconnected-(U5A-Opto_Out_C3-PadA92)") (class "Default")
      (node (ref "U5") (pin "A92") (pinfunction "Opto_Out_C3_A92") (pintype "passive"))
    )
    (net (code "186") (name "unconnected-(U5A-Opto_Out_C4-PadA96)") (class "Default")
      (node (ref "U5") (pin "A96") (pinfunction "Opto_Out_C4_A96") (pintype "passive"))
    )
    (net (code "187") (name "unconnected-(U5A-Opto_Out_C5-PadA100)") (class "Default")
      (node (ref "U5") (pin "A100") (pinfunction "Opto_Out_C5_A100") (pintype "passive"))
    )
    (net (code "188") (name "unconnected-(U5A-Opto_Out_C6-PadA104)") (class "Default")
      (node (ref "U5") (pin "A104") (pinfunction "Opto_Out_C6_A104") (pintype "passive"))
    )
    (net (code "189") (name "unconnected-(U5A-Opto_Out_C7-PadA108)") (class "Default")
      (node (ref "U5") (pin "A108") (pinfunction "Opto_Out_C7_A108") (pintype "passive"))
    )
    (net (code "190") (name "unconnected-(U5A-Opto_Out_E0-PadA82)") (class "Default")
      (node (ref "U5") (pin "A82") (pinfunction "Opto_Out_E0_A82") (pintype "passive"))
    )
    (net (code "191") (name "unconnected-(U5A-Opto_Out_E1-PadA86)") (class "Default")
      (node (ref "U5") (pin "A86") (pinfunction "Opto_Out_E1_A86") (pintype "passive"))
    )
    (net (code "192") (name "unconnected-(U5A-Opto_Out_E2-PadA90)") (class "Default")
      (node (ref "U5") (pin "A90") (pinfunction "Opto_Out_E2_A90") (pintype "passive"))
    )
    (net (code "193") (name "unconnected-(U5A-Opto_Out_E3-PadA94)") (class "Default")
      (node (ref "U5") (pin "A94") (pinfunction "Opto_Out_E3_A94") (pintype "passive"))
    )
    (net (code "194") (name "unconnected-(U5A-Opto_Out_E4-PadA98)") (class "Default")
      (node (ref "U5") (pin "A98") (pinfunction "Opto_Out_E4_A98") (pintype "passive"))
    )
    (net (code "195") (name "unconnected-(U5A-Opto_Out_E5-PadA102)") (class "Default")
      (node (ref "U5") (pin "A102") (pinfunction "Opto_Out_E5_A102") (pintype "passive"))
    )
    (net (code "196") (name "unconnected-(U5A-Opto_Out_E6-PadA106)") (class "Default")
      (node (ref "U5") (pin "A106") (pinfunction "Opto_Out_E6_A106") (pintype "passive"))
    )
    (net (code "197") (name "unconnected-(U5A-Opto_Out_E7-PadA110)") (class "Default")
      (node (ref "U5") (pin "A110") (pinfunction "Opto_Out_E7_A110") (pintype "passive"))
    )
    (net (code "198") (name "unconnected-(U5A-QuadA1+-PadA18)") (class "Default")
      (node (ref "U5") (pin "A18") (pinfunction "QuadA1+_A18") (pintype "passive"))
    )
    (net (code "199") (name "unconnected-(U5A-QuadA1--PadA20)") (class "Default")
      (node (ref "U5") (pin "A20") (pinfunction "QuadA1-_A20") (pintype "passive"))
    )
    (net (code "200") (name "unconnected-(U5A-QuadA2+-PadA30)") (class "Default")
      (node (ref "U5") (pin "A30") (pinfunction "QuadA2+_A30") (pintype "passive"))
    )
    (net (code "201") (name "unconnected-(U5A-QuadA2--PadA32)") (class "Default")
      (node (ref "U5") (pin "A32") (pinfunction "QuadA2-_A32") (pintype "passive"))
    )
    (net (code "202") (name "unconnected-(U5A-QuadA3+-PadA42)") (class "Default")
      (node (ref "U5") (pin "A42") (pinfunction "QuadA3+_A42") (pintype "passive"))
    )
    (net (code "203") (name "unconnected-(U5A-QuadA3--PadA44)") (class "Default")
      (node (ref "U5") (pin "A44") (pinfunction "QuadA3-_A44") (pintype "passive"))
    )
    (net (code "204") (name "unconnected-(U5A-QuadA4+-PadA54)") (class "Default")
      (node (ref "U5") (pin "A54") (pinfunction "QuadA4+_A54") (pintype "passive"))
    )
    (net (code "205") (name "unconnected-(U5A-QuadA4--PadA56)") (class "Default")
      (node (ref "U5") (pin "A56") (pinfunction "QuadA4-_A56") (pintype "passive"))
    )
    (net (code "206") (name "unconnected-(U5A-QuadB1+-PadA22)") (class "Default")
      (node (ref "U5") (pin "A22") (pinfunction "QuadB1+_A22") (pintype "passive"))
    )
    (net (code "207") (name "unconnected-(U5A-QuadB1--PadA24)") (class "Default")
      (node (ref "U5") (pin "A24") (pinfunction "QuadB1-_A24") (pintype "passive"))
    )
    (net (code "208") (name "unconnected-(U5A-QuadB2+-PadA34)") (class "Default")
      (node (ref "U5") (pin "A34") (pinfunction "QuadB2+_A34") (pintype "passive"))
    )
    (net (code "209") (name "unconnected-(U5A-QuadB2--PadA36)") (class "Default")
      (node (ref "U5") (pin "A36") (pinfunction "QuadB2-_A36") (pintype "passive"))
    )
    (net (code "210") (name "unconnected-(U5A-QuadB3+-PadA46)") (class "Default")
      (node (ref "U5") (pin "A46") (pinfunction "QuadB3+_A46") (pintype "passive"))
    )
    (net (code "211") (name "unconnected-(U5A-QuadB3--PadA48)") (class "Default")
      (node (ref "U5") (pin "A48") (pinfunction "QuadB3-_A48") (pintype "passive"))
    )
    (net (code "212") (name "unconnected-(U5A-QuadB4+-PadA58)") (class "Default")
      (node (ref "U5") (pin "A58") (pinfunction "QuadB4+_A58") (pintype "passive"))
    )
    (net (code "213") (name "unconnected-(U5A-QuadB4--PadA60)") (class "Default")
      (node (ref "U5") (pin "A60") (pinfunction "QuadB4-_A60") (pintype "passive"))
    )
    (net (code "214") (name "unconnected-(U5A-RS485_H-PadA57)") (class "Default")
      (node (ref "U5") (pin "A57") (pinfunction "RS485_H_A57") (pintype "passive"))
    )
    (net (code "215") (name "unconnected-(U5A-RS485_L-PadA59)") (class "Default")
      (node (ref "U5") (pin "A59") (pinfunction "RS485_L_A59") (pintype "passive"))
    )
    (net (code "216") (name "unconnected-(U5A-SPI_MISO-PadA65)") (class "Default")
      (node (ref "U5") (pin "A65") (pinfunction "SPI_MISO_A65") (pintype "passive"))
    )
    (net (code "217") (name "unconnected-(U5A-SPI_MOSI-PadA63)") (class "Default")
      (node (ref "U5") (pin "A63") (pinfunction "SPI_MOSI_A63") (pintype "passive"))
    )
    (net (code "218") (name "unconnected-(U5A-SPI_SClk-PadA61)") (class "Default")
      (node (ref "U5") (pin "A61") (pinfunction "SPI_SClk_A61") (pintype "passive"))
    )
    (net (code "219") (name "unconnected-(U5A-SPI_SS-PadA67)") (class "Default")
      (node (ref "U5") (pin "A67") (pinfunction "SPI_SS_A67") (pintype "passive"))
    )
    (net (code "220") (name "unconnected-(U5A-SPI_SSEL1-PadA69)") (class "Default")
      (node (ref "U5") (pin "A69") (pinfunction "SPI_SSEL1_A69") (pintype "passive"))
    )
    (net (code "221") (name "unconnected-(U5A-TDO-App_TDI-PadA72)") (class "Default")
      (node (ref "U5") (pin "A72") (pinfunction "TDO-App_TDI_A72") (pintype "passive"))
    )
    (net (code "222") (name "unconnected-(U5B-Direction1-PadB39)") (class "Default")
      (node (ref "U5") (pin "B39") (pinfunction "Direction1_B39") (pintype "passive"))
    )
    (net (code "223") (name "unconnected-(U5B-Direction2-PadB41)") (class "Default")
      (node (ref "U5") (pin "B41") (pinfunction "Direction2_B41") (pintype "passive"))
    )
    (net (code "224") (name "unconnected-(U5B-Direction3-PadB43)") (class "Default")
      (node (ref "U5") (pin "B43") (pinfunction "Direction3_B43") (pintype "passive"))
    )
    (net (code "225") (name "unconnected-(U5B-Direction4-PadB45)") (class "Default")
      (node (ref "U5") (pin "B45") (pinfunction "Direction4_B45") (pintype "passive"))
    )
    (net (code "226") (name "unconnected-(U5B-EtherGND-PadB69)") (class "Default")
      (node (ref "U5") (pin "B69") (pinfunction "EtherGND_B69") (pintype "passive"))
    )
    (net (code "227") (name "unconnected-(U5B-GP_Out_D24-PadB90)") (class "Default")
      (node (ref "U5") (pin "B90") (pinfunction "GP_Out_D24_B90") (pintype "passive"))
    )
    (net (code "228") (name "unconnected-(U5B-GP_Out_D25-PadB94)") (class "Default")
      (node (ref "U5") (pin "B94") (pinfunction "GP_Out_D25_B94") (pintype "passive"))
    )
    (net (code "229") (name "unconnected-(U5B-GP_Out_D26-PadB98)") (class "Default")
      (node (ref "U5") (pin "B98") (pinfunction "GP_Out_D26_B98") (pintype "passive"))
    )
    (net (code "230") (name "unconnected-(U5B-GP_Out_D27-PadB102)") (class "Default")
      (node (ref "U5") (pin "B102") (pinfunction "GP_Out_D27_B102") (pintype "passive"))
    )
    (net (code "231") (name "unconnected-(U5B-GP_Out_D28-PadB106)") (class "Default")
      (node (ref "U5") (pin "B106") (pinfunction "GP_Out_D28_B106") (pintype "passive"))
    )
    (net (code "232") (name "unconnected-(U5B-GP_Out_D29-PadB110)") (class "Default")
      (node (ref "U5") (pin "B110") (pinfunction "GP_Out_D29_B110") (pintype "passive"))
    )
    (net (code "233") (name "unconnected-(U5B-GP_Out_D30-PadB114)") (class "Default")
      (node (ref "U5") (pin "B114") (pinfunction "GP_Out_D30_B114") (pintype "passive"))
    )
    (net (code "234") (name "unconnected-(U5B-GP_Out_D31-PadB118)") (class "Default")
      (node (ref "U5") (pin "B118") (pinfunction "GP_Out_D31_B118") (pintype "passive"))
    )
    (net (code "235") (name "unconnected-(U5B-GP_Out_S24-PadB92)") (class "Default")
      (node (ref "U5") (pin "B92") (pinfunction "GP_Out_S24_B92") (pintype "passive"))
    )
    (net (code "236") (name "unconnected-(U5B-GP_Out_S25-PadB96)") (class "Default")
      (node (ref "U5") (pin "B96") (pinfunction "GP_Out_S25_B96") (pintype "passive"))
    )
    (net (code "237") (name "unconnected-(U5B-GP_Out_S26-PadB100)") (class "Default")
      (node (ref "U5") (pin "B100") (pinfunction "GP_Out_S26_B100") (pintype "passive"))
    )
    (net (code "238") (name "unconnected-(U5B-GP_Out_S27-PadB104)") (class "Default")
      (node (ref "U5") (pin "B104") (pinfunction "GP_Out_S27_B104") (pintype "passive"))
    )
    (net (code "239") (name "unconnected-(U5B-GP_Out_S28-PadB108)") (class "Default")
      (node (ref "U5") (pin "B108") (pinfunction "GP_Out_S28_B108") (pintype "passive"))
    )
    (net (code "240") (name "unconnected-(U5B-GP_Out_S29-PadB112)") (class "Default")
      (node (ref "U5") (pin "B112") (pinfunction "GP_Out_S29_B112") (pintype "passive"))
    )
    (net (code "241") (name "unconnected-(U5B-GP_Out_S30-PadB116)") (class "Default")
      (node (ref "U5") (pin "B116") (pinfunction "GP_Out_S30_B116") (pintype "passive"))
    )
    (net (code "242") (name "unconnected-(U5B-GP_Out_S31-PadB120)") (class "Default")
      (node (ref "U5") (pin "B120") (pinfunction "GP_Out_S31_B120") (pintype "passive"))
    )
    (net (code "243") (name "unconnected-(U5B-HomeCom-PadB9)") (class "Default")
      (node (ref "U5") (pin "B9") (pinfunction "HomeCom_B9") (pintype "passive"))
    )
    (net (code "244") (name "unconnected-(U5B-NegLimt1-PadB27)") (class "Default")
      (node (ref "U5") (pin "B27") (pinfunction "NegLimt1_B27") (pintype "passive"))
    )
    (net (code "245") (name "unconnected-(U5B-NegLimt2-PadB25)") (class "Default")
      (node (ref "U5") (pin "B25") (pinfunction "NegLimt2_B25") (pintype "passive"))
    )
    (net (code "246") (name "unconnected-(U5B-NegLimt3-PadB23)") (class "Default")
      (node (ref "U5") (pin "B23") (pinfunction "NegLimt3_B23") (pintype "passive"))
    )
    (net (code "247") (name "unconnected-(U5B-NegLimt4-PadB21)") (class "Default")
      (node (ref "U5") (pin "B21") (pinfunction "NegLimt4_B21") (pintype "passive"))
    )
    (net (code "248") (name "unconnected-(U5B-NegLimtCom-PadB29)") (class "Default")
      (node (ref "U5") (pin "B29") (pinfunction "NegLimtCom_B29") (pintype "passive"))
    )
    (net (code "249") (name "unconnected-(U5B-Opto_Input13-PadB95)") (class "Default")
      (node (ref "U5") (pin "B95") (pinfunction "Opto_Input13_B95") (pintype "passive"))
    )
    (net (code "250") (name "unconnected-(U5B-Opto_Input14-PadB97)") (class "Default")
      (node (ref "U5") (pin "B97") (pinfunction "Opto_Input14_B97") (pintype "passive"))
    )
    (net (code "251") (name "unconnected-(U5B-Opto_Input15-PadB99)") (class "Default")
      (node (ref "U5") (pin "B99") (pinfunction "Opto_Input15_B99") (pintype "passive"))
    )
    (net (code "252") (name "unconnected-(U5B-Opto_Input16-PadB103)") (class "Default")
      (node (ref "U5") (pin "B103") (pinfunction "Opto_Input16_B103") (pintype "passive"))
    )
    (net (code "253") (name "unconnected-(U5B-Opto_Input17-PadB105)") (class "Default")
      (node (ref "U5") (pin "B105") (pinfunction "Opto_Input17_B105") (pintype "passive"))
    )
    (net (code "254") (name "unconnected-(U5B-Opto_Input18-PadB107)") (class "Default")
      (node (ref "U5") (pin "B107") (pinfunction "Opto_Input18_B107") (pintype "passive"))
    )
    (net (code "255") (name "unconnected-(U5B-Opto_Input19-PadB109)") (class "Default")
      (node (ref "U5") (pin "B109") (pinfunction "Opto_Input19_B109") (pintype "passive"))
    )
    (net (code "256") (name "unconnected-(U5B-Opto_Input20-PadB113)") (class "Default")
      (node (ref "U5") (pin "B113") (pinfunction "Opto_Input20_B113") (pintype "passive"))
    )
    (net (code "257") (name "unconnected-(U5B-Opto_Input21-PadB115)") (class "Default")
      (node (ref "U5") (pin "B115") (pinfunction "Opto_Input21_B115") (pintype "passive"))
    )
    (net (code "258") (name "unconnected-(U5B-Opto_Input22-PadB117)") (class "Default")
      (node (ref "U5") (pin "B117") (pinfunction "Opto_Input22_B117") (pintype "passive"))
    )
    (net (code "259") (name "unconnected-(U5B-Opto_Input23-PadB119)") (class "Default")
      (node (ref "U5") (pin "B119") (pinfunction "Opto_Input23_B119") (pintype "passive"))
    )
    (net (code "260") (name "unconnected-(U5B-Opto_Input_Com4-PadB101)") (class "Default")
      (node (ref "U5") (pin "B101") (pinfunction "Opto_Input_Com4_B101") (pintype "passive"))
    )
    (net (code "261") (name "unconnected-(U5B-Opto_Input_Com5-PadB111)") (class "Default")
      (node (ref "U5") (pin "B111") (pinfunction "Opto_Input_Com5_B111") (pintype "passive"))
    )
    (net (code "262") (name "unconnected-(U5B-PosLimt1-PadB17)") (class "Default")
      (node (ref "U5") (pin "B17") (pinfunction "PosLimt1_B17") (pintype "passive"))
    )
    (net (code "263") (name "unconnected-(U5B-PosLimt2-PadB15)") (class "Default")
      (node (ref "U5") (pin "B15") (pinfunction "PosLimt2_B15") (pintype "passive"))
    )
    (net (code "264") (name "unconnected-(U5B-PosLimt3-PadB13)") (class "Default")
      (node (ref "U5") (pin "B13") (pinfunction "PosLimt3_B13") (pintype "passive"))
    )
    (net (code "265") (name "unconnected-(U5B-PosLimt4-PadB11)") (class "Default")
      (node (ref "U5") (pin "B11") (pinfunction "PosLimt4_B11") (pintype "passive"))
    )
    (net (code "266") (name "unconnected-(U5B-PosLimtCom-PadB19)") (class "Default")
      (node (ref "U5") (pin "B19") (pinfunction "PosLimtCom_B19") (pintype "passive"))
    )
    (net (code "267") (name "unconnected-(U5B-Step1-PadB31)") (class "Default")
      (node (ref "U5") (pin "B31") (pinfunction "Step1_B31") (pintype "passive"))
    )
    (net (code "268") (name "unconnected-(U5B-Step2-PadB33)") (class "Default")
      (node (ref "U5") (pin "B33") (pinfunction "Step2_B33") (pintype "passive"))
    )
    (net (code "269") (name "unconnected-(U5B-Step3-PadB35)") (class "Default")
      (node (ref "U5") (pin "B35") (pinfunction "Step3_B35") (pintype "passive"))
    )
    (net (code "270") (name "unconnected-(U5B-Step4-PadB37)") (class "Default")
      (node (ref "U5") (pin "B37") (pinfunction "Step4_B37") (pintype "passive"))
    )
    (net (code "271") (name "unconnected-(U5B-~Home1-PadB7)") (class "Default")
      (node (ref "U5") (pin "B7") (pinfunction "~Home1_B7") (pintype "passive"))
    )
    (net (code "272") (name "unconnected-(U5B-~Home2-PadB5)") (class "Default")
      (node (ref "U5") (pin "B5") (pinfunction "~Home2_B5") (pintype "passive"))
    )
    (net (code "273") (name "unconnected-(U5B-~Home3-PadB3)") (class "Default")
      (node (ref "U5") (pin "B3") (pinfunction "~Home3_B3") (pintype "passive"))
    )
    (net (code "274") (name "unconnected-(U5B-~Home4-PadB1)") (class "Default")
      (node (ref "U5") (pin "B1") (pinfunction "~Home4_B1") (pintype "passive"))
    )
    (net (code "275") (name "unconnected-(U6-NC-Pad5)") (class "Default")
      (node (ref "U6") (pin "5") (pinfunction "NC_5") (pintype "passive"))
    )
    (net (code "276") (name "unconnected-(U6-VOSTRIM-Pad1)") (class "Default")
      (node (ref "U6") (pin "1") (pinfunction "VOSTRIM_1") (pintype "passive"))
    )
    (net (code "277") (name "unconnected-(U6-VOSTRIM-Pad8)") (class "Default")
      (node (ref "U6") (pin "8") (pinfunction "VOSTRIM_8") (pintype "passive"))
    )
  )
)
